# HeadController.net
KiCad netlist of a schematic drawn in Altium Designer
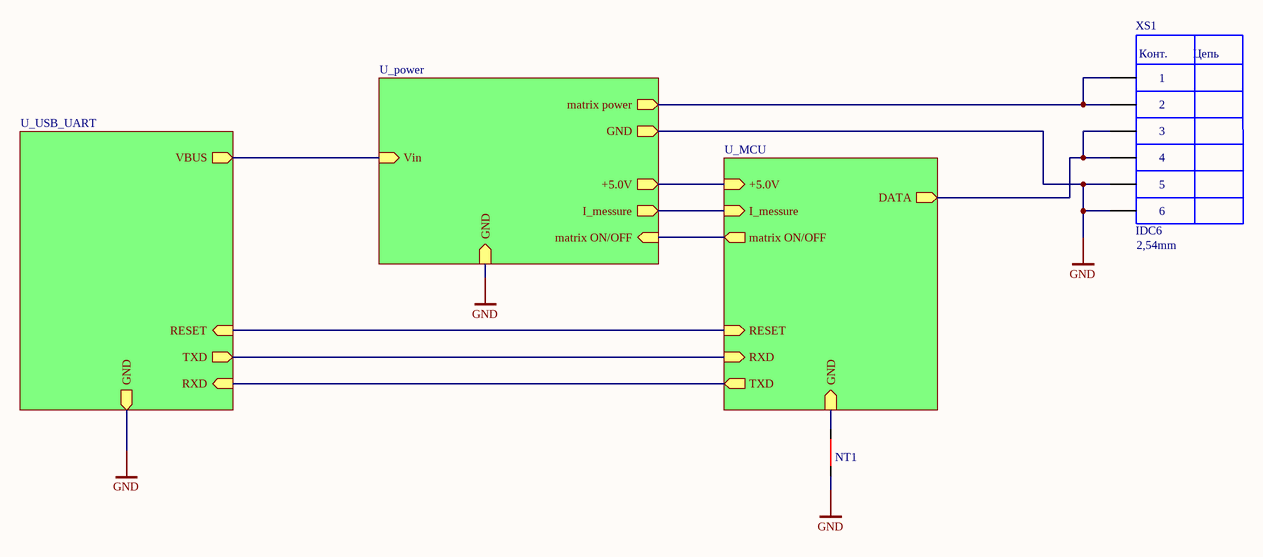
[diagram p0: HeadController.SchDoc]

(export (version "E")
  (design (tool "Eeschema 10.0.6"))
  (components
    (comp (ref "NT1") (value "~") (footprint "NT") (libsource (lib "MechanikLibrary") (part "NT")))
    (comp (ref "XS1")
      (value "IDC6")
      (footprint "IDC-6 (2.54) (end face)")
      (fields (field (name "PACKAGE") "2,54mm"))
      (libsource (lib "MechanikLibrary") (part "IDC6"))
    )
  )
  (nets
    (net (code "2") (name "/DATA") (class "Default")
      (node (ref "XS1") (pin "3") (pintype "passive"))
      (node (ref "XS1") (pin "4") (pintype "passive"))
    )
    (net (code "3") (name "/GND") (class "Default") (node (ref "NT1") (pin "1") (pintype "passive")))
    (net (code "10") (name "/matrix power") (class "Default")
      (node (ref "XS1") (pin "1") (pintype "passive"))
      (node (ref "XS1") (pin "2") (pintype "passive"))
    )
    (net (code "11") (name "GND") (class "Default")
      (node (ref "NT1") (pin "2") (pintype "passive"))
      (node (ref "XS1") (pin "5") (pintype "passive"))
      (node (ref "XS1") (pin "6") (pintype "passive"))
    )
  )
)
